# mcb-enhancer-v3.net
KiCad netlist of a schematic drawn in EAGLE
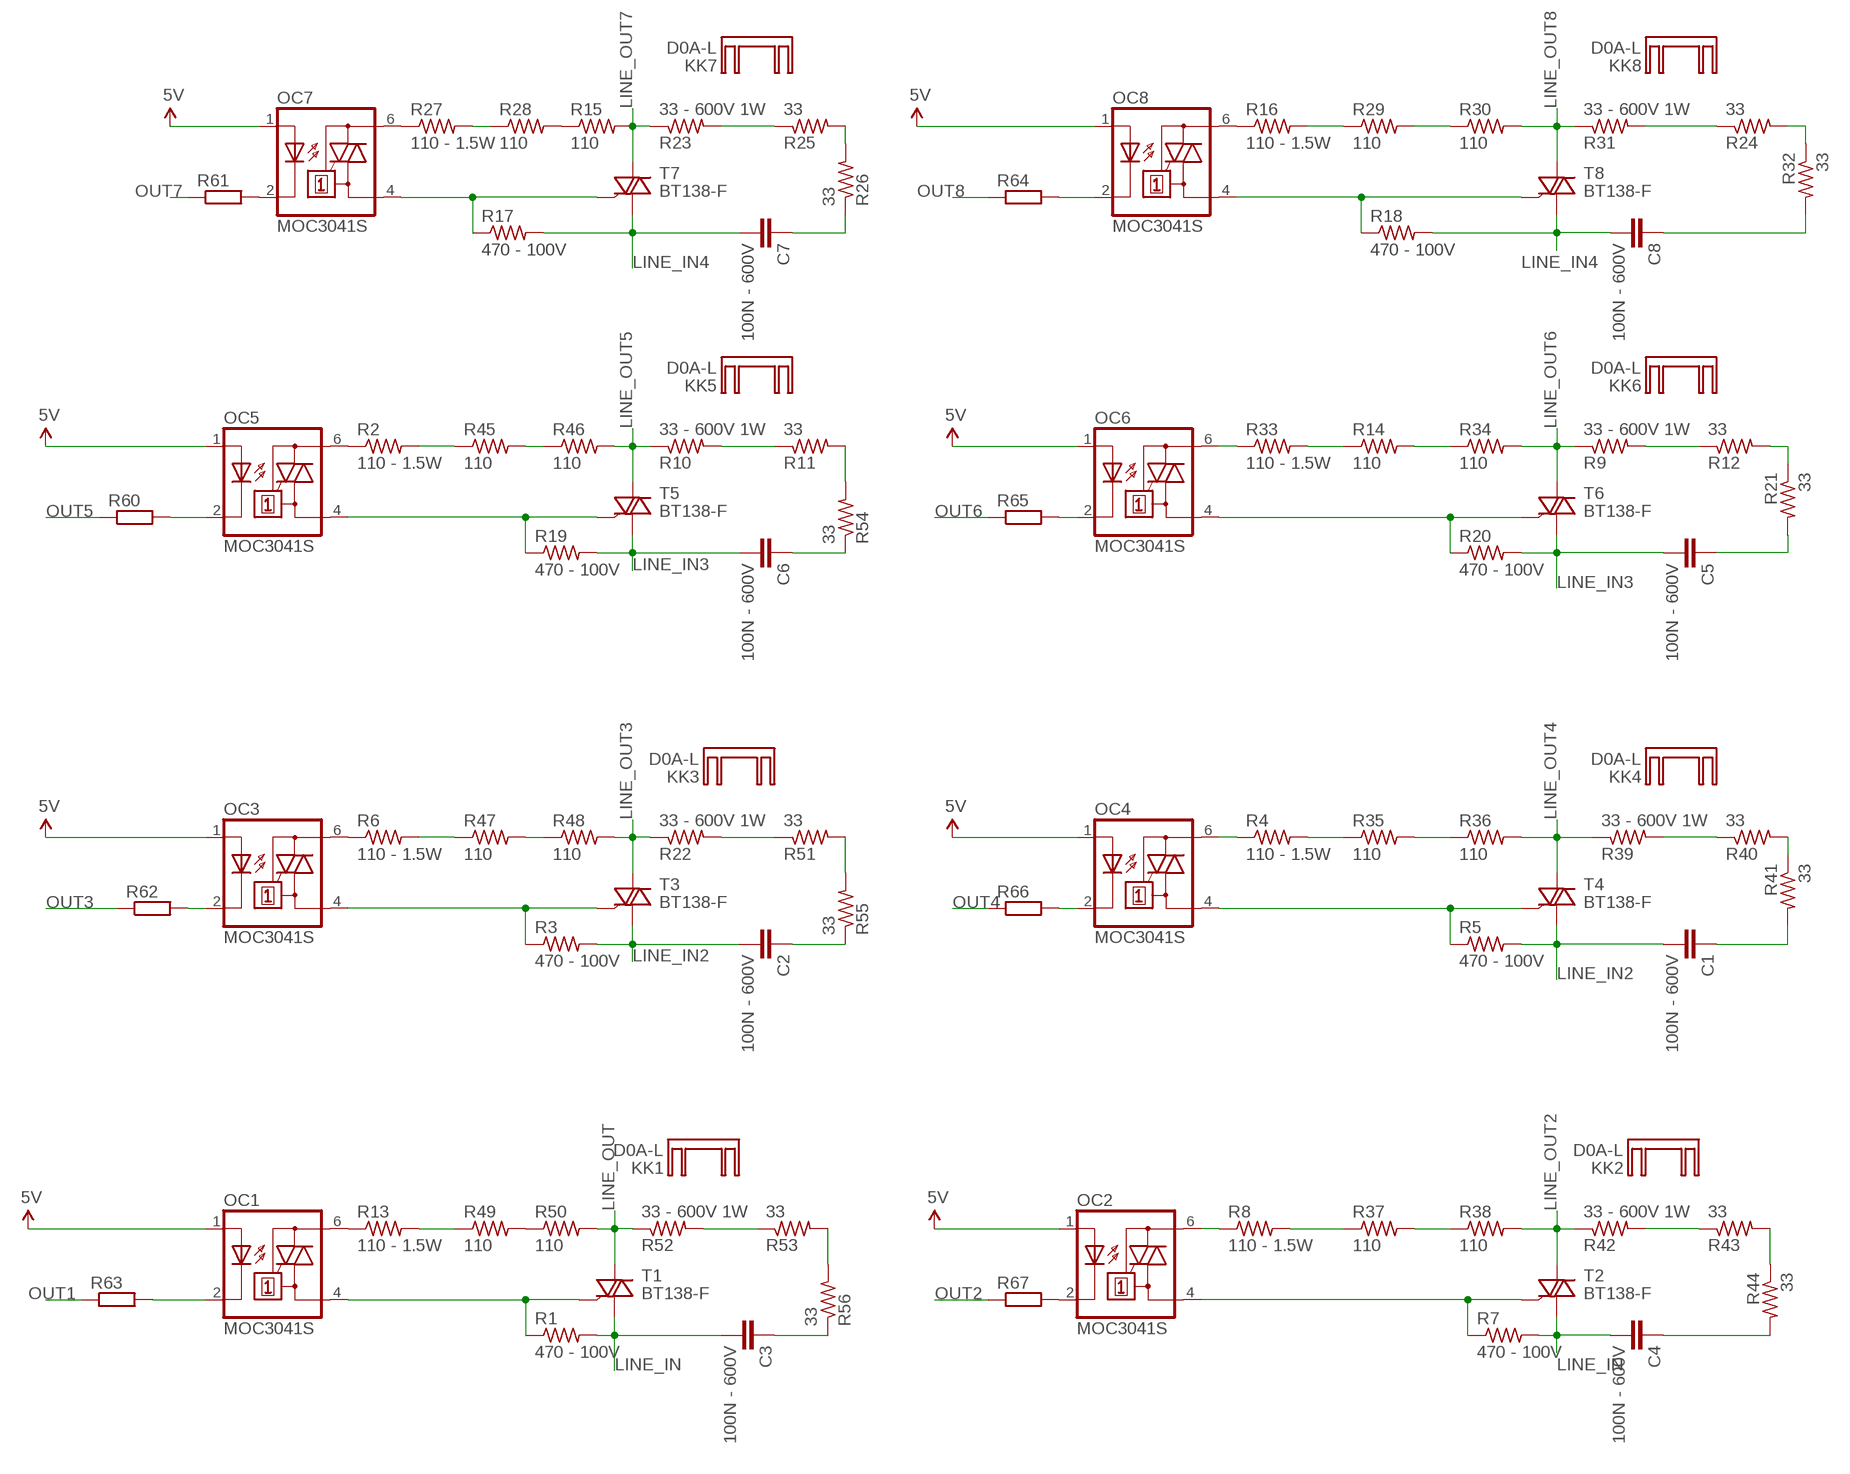
[diagram p0: schematic, sheet 1]

(export (version "E")
  (design (tool "Eeschema 10.0.6"))
  (components
    (comp (ref "C1")
      (value "100N - 600V")
      (footprint "eagle-import:C050-030X075")
      (libsource (lib "eagle-import") (part "C-EU050-030X075"))
    )
    (comp (ref "C2")
      (value "100N - 600V")
      (footprint "eagle-import:C050-030X075")
      (libsource (lib "eagle-import") (part "C-EU050-030X075"))
    )
    (comp (ref "C3")
      (value "100N - 600V")
      (footprint "eagle-import:C050-030X075")
      (libsource (lib "eagle-import") (part "C-EU050-030X075"))
    )
    (comp (ref "C4")
      (value "100N - 600V")
      (footprint "eagle-import:C050-030X075")
      (libsource (lib "eagle-import") (part "C-EU050-030X075"))
    )
    (comp (ref "C5")
      (value "100N - 600V")
      (footprint "eagle-import:C050-030X075")
      (libsource (lib "eagle-import") (part "C-EU050-030X075"))
    )
    (comp (ref "C6")
      (value "100N - 600V")
      (footprint "eagle-import:C050-030X075")
      (libsource (lib "eagle-import") (part "C-EU050-030X075"))
    )
    (comp (ref "C7")
      (value "100N - 600V")
      (footprint "eagle-import:C050-030X075")
      (libsource (lib "eagle-import") (part "C-EU050-030X075"))
    )
    (comp (ref "C8")
      (value "100N - 600V")
      (footprint "eagle-import:C050-030X075")
      (libsource (lib "eagle-import") (part "C-EU050-030X075"))
    )
    (comp (ref "KK1")
      (value "D0A-L")
      (footprint "eagle-import:D02A-L")
      (libsource (lib "eagle-import") (part "D0A-L"))
    )
    (comp (ref "KK2")
      (value "D0A-L")
      (footprint "eagle-import:D02A-L")
      (libsource (lib "eagle-import") (part "D0A-L"))
    )
    (comp (ref "KK3")
      (value "D0A-L")
      (footprint "eagle-import:D02A-L")
      (libsource (lib "eagle-import") (part "D0A-L"))
    )
    (comp (ref "KK4")
      (value "D0A-L")
      (footprint "eagle-import:D02A-L")
      (libsource (lib "eagle-import") (part "D0A-L"))
    )
    (comp (ref "KK5")
      (value "D0A-L")
      (footprint "eagle-import:D02A-L")
      (libsource (lib "eagle-import") (part "D0A-L"))
    )
    (comp (ref "KK6")
      (value "D0A-L")
      (footprint "eagle-import:D02A-L")
      (libsource (lib "eagle-import") (part "D0A-L"))
    )
    (comp (ref "KK7")
      (value "D0A-L")
      (footprint "eagle-import:D02A-L")
      (libsource (lib "eagle-import") (part "D0A-L"))
    )
    (comp (ref "KK8")
      (value "D0A-L")
      (footprint "eagle-import:D02A-L")
      (libsource (lib "eagle-import") (part "D0A-L"))
    )
    (comp (ref "OC1")
      (value "MOC3041S")
      (footprint "eagle-import:DIL6-SMD")
      (fields
        (field (name "MF") "FAIRCHILD SEMICONDUCTOR")
        (field (name "MPN") "MOC3041S-M")
        (field (name "MPN_1") "MOC3033S-M")
        (field (name "OC_FARNELL") "unknown")
        (field (name "OC_NEWARK") "05C2878")
      )
      (libsource (lib "eagle-import") (part "MOC30S41"))
    )
    (comp (ref "OC2")
      (value "MOC3041S")
      (footprint "eagle-import:DIL6-SMD")
      (fields
        (field (name "MF") "FAIRCHILD SEMICONDUCTOR")
        (field (name "MPN") "MOC3041S-M")
        (field (name "MPN_1") "MOC3033S-M")
        (field (name "OC_FARNELL") "unknown")
        (field (name "OC_NEWARK") "05C2878")
      )
      (libsource (lib "eagle-import") (part "MOC30S41"))
    )
    (comp (ref "OC3")
      (value "MOC3041S")
      (footprint "eagle-import:DIL6-SMD")
      (fields
        (field (name "MF") "FAIRCHILD SEMICONDUCTOR")
        (field (name "MPN") "MOC3041S-M")
        (field (name "MPN_1") "MOC3033S-M")
        (field (name "OC_FARNELL") "unknown")
        (field (name "OC_NEWARK") "05C2878")
      )
      (libsource (lib "eagle-import") (part "MOC30S41"))
    )
    (comp (ref "OC4")
      (value "MOC3041S")
      (footprint "eagle-import:DIL6-SMD")
      (fields
        (field (name "MF") "FAIRCHILD SEMICONDUCTOR")
        (field (name "MPN") "MOC3041S-M")
        (field (name "MPN_1") "MOC3033S-M")
        (field (name "OC_FARNELL") "unknown")
        (field (name "OC_NEWARK") "05C2878")
      )
      (libsource (lib "eagle-import") (part "MOC30S41"))
    )
    (comp (ref "OC5")
      (value "MOC3041S")
      (footprint "eagle-import:DIL6-SMD")
      (fields
        (field (name "MF") "FAIRCHILD SEMICONDUCTOR")
        (field (name "MPN") "MOC3041S-M")
        (field (name "MPN_1") "MOC3033S-M")
        (field (name "OC_FARNELL") "unknown")
        (field (name "OC_NEWARK") "05C2878")
      )
      (libsource (lib "eagle-import") (part "MOC30S41"))
    )
    (comp (ref "OC6")
      (value "MOC3041S")
      (footprint "eagle-import:DIL6-SMD")
      (fields
        (field (name "MF") "FAIRCHILD SEMICONDUCTOR")
        (field (name "MPN") "MOC3041S-M")
        (field (name "MPN_1") "MOC3033S-M")
        (field (name "OC_FARNELL") "unknown")
        (field (name "OC_NEWARK") "05C2878")
      )
      (libsource (lib "eagle-import") (part "MOC30S41"))
    )
    (comp (ref "OC7")
      (value "MOC3041S")
      (footprint "eagle-import:DIL6-SMD")
      (fields
        (field (name "MF") "FAIRCHILD SEMICONDUCTOR")
        (field (name "MPN") "MOC3041S-M")
        (field (name "MPN_1") "MOC3033S-M")
        (field (name "OC_FARNELL") "unknown")
        (field (name "OC_NEWARK") "05C2878")
      )
      (libsource (lib "eagle-import") (part "MOC30S41"))
    )
    (comp (ref "OC8")
      (value "MOC3041S")
      (footprint "eagle-import:DIL6-SMD")
      (fields
        (field (name "MF") "FAIRCHILD SEMICONDUCTOR")
        (field (name "MPN") "MOC3041S-M")
        (field (name "MPN_1") "MOC3033S-M")
        (field (name "OC_FARNELL") "unknown")
        (field (name "OC_NEWARK") "05C2878")
      )
      (libsource (lib "eagle-import") (part "MOC30S41"))
    )
    (comp (ref "R1")
      (value "470 - 100V")
      (footprint "eagle-import:R1206")
      (libsource (lib "eagle-import") (part "R-US_R1206"))
    )
    (comp (ref "R2")
      (value "110 - 1.5W")
      (footprint "eagle-import:R2512")
      (libsource (lib "eagle-import") (part "R-US_R2512"))
    )
    (comp (ref "R3")
      (value "470 - 100V")
      (footprint "eagle-import:R1206")
      (libsource (lib "eagle-import") (part "R-US_R1206"))
    )
    (comp (ref "R4")
      (value "110 - 1.5W")
      (footprint "eagle-import:R2512")
      (libsource (lib "eagle-import") (part "R-US_R2512"))
    )
    (comp (ref "R5")
      (value "470 - 100V")
      (footprint "eagle-import:R1206")
      (libsource (lib "eagle-import") (part "R-US_R1206"))
    )
    (comp (ref "R6")
      (value "110 - 1.5W")
      (footprint "eagle-import:R2512")
      (libsource (lib "eagle-import") (part "R-US_R2512"))
    )
    (comp (ref "R7")
      (value "470 - 100V")
      (footprint "eagle-import:R1206")
      (libsource (lib "eagle-import") (part "R-US_R1206"))
    )
    (comp (ref "R8")
      (value "110 - 1.5W")
      (footprint "eagle-import:R2512")
      (libsource (lib "eagle-import") (part "R-US_R2512"))
    )
    (comp (ref "R9")
      (value "33 - 600V 1W")
      (footprint "eagle-import:R1206")
      (libsource (lib "eagle-import") (part "R-US_R1206"))
    )
    (comp (ref "R10")
      (value "33 - 600V 1W")
      (footprint "eagle-import:R1206")
      (libsource (lib "eagle-import") (part "R-US_R1206"))
    )
    (comp (ref "R11")
      (value "33")
      (footprint "eagle-import:R1206")
      (libsource (lib "eagle-import") (part "R-US_R1206"))
    )
    (comp (ref "R12")
      (value "33")
      (footprint "eagle-import:R1206")
      (libsource (lib "eagle-import") (part "R-US_R1206"))
    )
    (comp (ref "R13")
      (value "110 - 1.5W")
      (footprint "eagle-import:R2512")
      (libsource (lib "eagle-import") (part "R-US_R2512"))
    )
    (comp (ref "R14")
      (value "110")
      (footprint "eagle-import:R2512")
      (libsource (lib "eagle-import") (part "R-US_R2512"))
    )
    (comp (ref "R15")
      (value "110")
      (footprint "eagle-import:R2512")
      (libsource (lib "eagle-import") (part "R-US_R2512"))
    )
    (comp (ref "R16")
      (value "110 - 1.5W")
      (footprint "eagle-import:R2512")
      (libsource (lib "eagle-import") (part "R-US_R2512"))
    )
    (comp (ref "R17")
      (value "470 - 100V")
      (footprint "eagle-import:R1206")
      (libsource (lib "eagle-import") (part "R-US_R1206"))
    )
    (comp (ref "R18")
      (value "470 - 100V")
      (footprint "eagle-import:R1206")
      (libsource (lib "eagle-import") (part "R-US_R1206"))
    )
    (comp (ref "R19")
      (value "470 - 100V")
      (footprint "eagle-import:R1206")
      (libsource (lib "eagle-import") (part "R-US_R1206"))
    )
    (comp (ref "R20")
      (value "470 - 100V")
      (footprint "eagle-import:R1206")
      (libsource (lib "eagle-import") (part "R-US_R1206"))
    )
    (comp (ref "R21")
      (value "33")
      (footprint "eagle-import:R1206")
      (libsource (lib "eagle-import") (part "R-US_R1206"))
    )
    (comp (ref "R22")
      (value "33 - 600V 1W")
      (footprint "eagle-import:R1206")
      (libsource (lib "eagle-import") (part "R-US_R1206"))
    )
    (comp (ref "R23")
      (value "33 - 600V 1W")
      (footprint "eagle-import:R1206")
      (libsource (lib "eagle-import") (part "R-US_R1206"))
    )
    (comp (ref "R24")
      (value "33")
      (footprint "eagle-import:R1206")
      (libsource (lib "eagle-import") (part "R-US_R1206"))
    )
    (comp (ref "R25")
      (value "33")
      (footprint "eagle-import:R1206")
      (libsource (lib "eagle-import") (part "R-US_R1206"))
    )
    (comp (ref "R26")
      (value "33")
      (footprint "eagle-import:R1206")
      (libsource (lib "eagle-import") (part "R-US_R1206"))
    )
    (comp (ref "R27")
      (value "110 - 1.5W")
      (footprint "eagle-import:R2512")
      (libsource (lib "eagle-import") (part "R-US_R2512"))
    )
    (comp (ref "R28")
      (value "110")
      (footprint "eagle-import:R2512")
      (libsource (lib "eagle-import") (part "R-US_R2512"))
    )
    (comp (ref "R29")
      (value "110")
      (footprint "eagle-import:R2512")
      (libsource (lib "eagle-import") (part "R-US_R2512"))
    )
    (comp (ref "R30")
      (value "110")
      (footprint "eagle-import:R2512")
      (libsource (lib "eagle-import") (part "R-US_R2512"))
    )
    (comp (ref "R31")
      (value "33 - 600V 1W")
      (footprint "eagle-import:R1206")
      (libsource (lib "eagle-import") (part "R-US_R1206"))
    )
    (comp (ref "R32")
      (value "33")
      (footprint "eagle-import:R1206")
      (libsource (lib "eagle-import") (part "R-US_R1206"))
    )
    (comp (ref "R33")
      (value "110 - 1.5W")
      (footprint "eagle-import:R2512")
      (libsource (lib "eagle-import") (part "R-US_R2512"))
    )
    (comp (ref "R34")
      (value "110")
      (footprint "eagle-import:R2512")
      (libsource (lib "eagle-import") (part "R-US_R2512"))
    )
    (comp (ref "R35")
      (value "110")
      (footprint "eagle-import:R2512")
      (libsource (lib "eagle-import") (part "R-US_R2512"))
    )
    (comp (ref "R36")
      (value "110")
      (footprint "eagle-import:R2512")
      (libsource (lib "eagle-import") (part "R-US_R2512"))
    )
    (comp (ref "R37")
      (value "110")
      (footprint "eagle-import:R2512")
      (libsource (lib "eagle-import") (part "R-US_R2512"))
    )
    (comp (ref "R38")
      (value "110")
      (footprint "eagle-import:R2512")
      (libsource (lib "eagle-import") (part "R-US_R2512"))
    )
    (comp (ref "R39")
      (value "33 - 600V 1W")
      (footprint "eagle-import:R1206")
      (libsource (lib "eagle-import") (part "R-US_R1206"))
    )
    (comp (ref "R40")
      (value "33")
      (footprint "eagle-import:R1206")
      (libsource (lib "eagle-import") (part "R-US_R1206"))
    )
    (comp (ref "R41")
      (value "33")
      (footprint "eagle-import:R1206")
      (libsource (lib "eagle-import") (part "R-US_R1206"))
    )
    (comp (ref "R42")
      (value "33 - 600V 1W")
      (footprint "eagle-import:R1206")
      (libsource (lib "eagle-import") (part "R-US_R1206"))
    )
    (comp (ref "R43")
      (value "33")
      (footprint "eagle-import:R1206")
      (libsource (lib "eagle-import") (part "R-US_R1206"))
    )
    (comp (ref "R44")
      (value "33")
      (footprint "eagle-import:R1206")
      (libsource (lib "eagle-import") (part "R-US_R1206"))
    )
    (comp (ref "R45")
      (value "110")
      (footprint "eagle-import:R2512")
      (libsource (lib "eagle-import") (part "R-US_R2512"))
    )
    (comp (ref "R46")
      (value "110")
      (footprint "eagle-import:R2512")
      (libsource (lib "eagle-import") (part "R-US_R2512"))
    )
    (comp (ref "R47")
      (value "110")
      (footprint "eagle-import:R2512")
      (libsource (lib "eagle-import") (part "R-US_R2512"))
    )
    (comp (ref "R48")
      (value "110")
      (footprint "eagle-import:R2512")
      (libsource (lib "eagle-import") (part "R-US_R2512"))
    )
    (comp (ref "R49")
      (value "110")
      (footprint "eagle-import:R2512")
      (libsource (lib "eagle-import") (part "R-US_R2512"))
    )
    (comp (ref "R50")
      (value "110")
      (footprint "eagle-import:R2512")
      (libsource (lib "eagle-import") (part "R-US_R2512"))
    )
    (comp (ref "R51")
      (value "33")
      (footprint "eagle-import:R1206")
      (libsource (lib "eagle-import") (part "R-US_R1206"))
    )
    (comp (ref "R52")
      (value "33 - 600V 1W")
      (footprint "eagle-import:R1206")
      (libsource (lib "eagle-import") (part "R-US_R1206"))
    )
    (comp (ref "R53")
      (value "33")
      (footprint "eagle-import:R1206")
      (libsource (lib "eagle-import") (part "R-US_R1206"))
    )
    (comp (ref "R54")
      (value "33")
      (footprint "eagle-import:R1206")
      (libsource (lib "eagle-import") (part "R-US_R1206"))
    )
    (comp (ref "R55")
      (value "33")
      (footprint "eagle-import:R1206")
      (libsource (lib "eagle-import") (part "R-US_R1206"))
    )
    (comp (ref "R56")
      (value "33")
      (footprint "eagle-import:R1206")
      (libsource (lib "eagle-import") (part "R-US_R1206"))
    )
    (comp (ref "R60")
      (value "R-EU_R0603")
      (footprint "eagle-import:R0603")
      (libsource (lib "eagle-import") (part "R-EU_R0603"))
    )
    (comp (ref "R61")
      (value "R-EU_R0603")
      (footprint "eagle-import:R0603")
      (libsource (lib "eagle-import") (part "R-EU_R0603"))
    )
    (comp (ref "R62")
      (value "R-EU_R0603")
      (footprint "eagle-import:R0603")
      (libsource (lib "eagle-import") (part "R-EU_R0603"))
    )
    (comp (ref "R63")
      (value "R-EU_R0603")
      (footprint "eagle-import:R0603")
      (libsource (lib "eagle-import") (part "R-EU_R0603"))
    )
    (comp (ref "R64")
      (value "R-EU_R0603")
      (footprint "eagle-import:R0603")
      (libsource (lib "eagle-import") (part "R-EU_R0603"))
    )
    (comp (ref "R65")
      (value "R-EU_R0603")
      (footprint "eagle-import:R0603")
      (libsource (lib "eagle-import") (part "R-EU_R0603"))
    )
    (comp (ref "R66")
      (value "R-EU_R0603")
      (footprint "eagle-import:R0603")
      (libsource (lib "eagle-import") (part "R-EU_R0603"))
    )
    (comp (ref "R67")
      (value "R-EU_R0603")
      (footprint "eagle-import:R0603")
      (libsource (lib "eagle-import") (part "R-EU_R0603"))
    )
    (comp (ref "T1")
      (value "BT138-F")
      (footprint "eagle-import:TO220BF")
      (libsource (lib "eagle-import") (part "BT138-F"))
    )
    (comp (ref "T2")
      (value "BT138-F")
      (footprint "eagle-import:TO220BF")
      (libsource (lib "eagle-import") (part "BT138-F"))
    )
    (comp (ref "T3")
      (value "BT138-F")
      (footprint "eagle-import:TO220BF")
      (libsource (lib "eagle-import") (part "BT138-F"))
    )
    (comp (ref "T4")
      (value "BT138-F")
      (footprint "eagle-import:TO220BF")
      (libsource (lib "eagle-import") (part "BT138-F"))
    )
    (comp (ref "T5")
      (value "BT138-F")
      (footprint "eagle-import:TO220BF")
      (libsource (lib "eagle-import") (part "BT138-F"))
    )
    (comp (ref "T6")
      (value "BT138-F")
      (footprint "eagle-import:TO220BF")
      (libsource (lib "eagle-import") (part "BT138-F"))
    )
    (comp (ref "T7")
      (value "BT138-F")
      (footprint "eagle-import:TO220BF")
      (libsource (lib "eagle-import") (part "BT138-F"))
    )
    (comp (ref "T8")
      (value "BT138-F")
      (footprint "eagle-import:TO220BF")
      (libsource (lib "eagle-import") (part "BT138-F"))
    )
  )
  (nets
    (net (code "1") (name "/LINE_IN") (class "Default")
      (node (ref "C3") (pin "2") (pinfunction "2_2") (pintype "passive"))
      (node (ref "C4") (pin "2") (pinfunction "2_2") (pintype "passive"))
      (node (ref "R1") (pin "2") (pinfunction "2_2") (pintype "passive"))
      (node (ref "R7") (pin "2") (pinfunction "2_2") (pintype "passive"))
      (node (ref "T1") (pin "T1") (pinfunction "A1_T1") (pintype "passive"))
      (node (ref "T2") (pin "T1") (pinfunction "A1_T1") (pintype "passive"))
    )
    (net (code "2") (name "/LINE_IN2") (class "Default")
      (node (ref "C1") (pin "2") (pinfunction "2_2") (pintype "passive"))
      (node (ref "C2") (pin "2") (pinfunction "2_2") (pintype "passive"))
      (node (ref "R3") (pin "2") (pinfunction "2_2") (pintype "passive"))
      (node (ref "R5") (pin "2") (pinfunction "2_2") (pintype "passive"))
      (node (ref "T3") (pin "T1") (pinfunction "A1_T1") (pintype "passive"))
      (node (ref "T4") (pin "T1") (pinfunction "A1_T1") (pintype "passive"))
    )
    (net (code "3") (name "/LINE_IN3") (class "Default")
      (node (ref "C5") (pin "2") (pinfunction "2_2") (pintype "passive"))
      (node (ref "C6") (pin "2") (pinfunction "2_2") (pintype "passive"))
      (node (ref "R19") (pin "2") (pinfunction "2_2") (pintype "passive"))
      (node (ref "R20") (pin "2") (pinfunction "2_2") (pintype "passive"))
      (node (ref "T5") (pin "T1") (pinfunction "A1_T1") (pintype "passive"))
      (node (ref "T6") (pin "T1") (pinfunction "A1_T1") (pintype "passive"))
    )
    (net (code "4") (name "/LINE_IN4") (class "Default")
      (node (ref "C7") (pin "2") (pinfunction "2_2") (pintype "passive"))
      (node (ref "C8") (pin "2") (pinfunction "2_2") (pintype "passive"))
      (node (ref "R17") (pin "2") (pinfunction "2_2") (pintype "passive"))
      (node (ref "R18") (pin "2") (pinfunction "2_2") (pintype "passive"))
      (node (ref "T7") (pin "T1") (pinfunction "A1_T1") (pintype "passive"))
      (node (ref "T8") (pin "T1") (pinfunction "A1_T1") (pintype "passive"))
    )
    (net (code "5") (name "/LINE_OUT") (class "Default")
      (node (ref "R50") (pin "2") (pinfunction "2_2") (pintype "passive"))
      (node (ref "R52") (pin "1") (pinfunction "1_1") (pintype "passive"))
      (node (ref "T1") (pin "T2") (pinfunction "A2_T2") (pintype "passive"))
    )
    (net (code "6") (name "/LINE_OUT2") (class "Default")
      (node (ref "R38") (pin "2") (pinfunction "2_2") (pintype "passive"))
      (node (ref "R42") (pin "1") (pinfunction "1_1") (pintype "passive"))
      (node (ref "T2") (pin "T2") (pinfunction "A2_T2") (pintype "passive"))
    )
    (net (code "7") (name "/LINE_OUT3") (class "Default")
      (node (ref "R22") (pin "1") (pinfunction "1_1") (pintype "passive"))
      (node (ref "R48") (pin "2") (pinfunction "2_2") (pintype "passive"))
      (node (ref "T3") (pin "T2") (pinfunction "A2_T2") (pintype "passive"))
    )
    (net (code "8") (name "/LINE_OUT4") (class "Default")
      (node (ref "R36") (pin "2") (pinfunction "2_2") (pintype "passive"))
      (node (ref "R39") (pin "1") (pinfunction "1_1") (pintype "passive"))
      (node (ref "T4") (pin "T2") (pinfunction "A2_T2") (pintype "passive"))
    )
    (net (code "9") (name "/LINE_OUT5") (class "Default")
      (node (ref "R10") (pin "1") (pinfunction "1_1") (pintype "passive"))
      (node (ref "R46") (pin "2") (pinfunction "2_2") (pintype "passive"))
      (node (ref "T5") (pin "T2") (pinfunction "A2_T2") (pintype "passive"))
    )
    (net (code "10") (name "/LINE_OUT6") (class "Default")
      (node (ref "R34") (pin "2") (pinfunction "2_2") (pintype "passive"))
      (node (ref "R9") (pin "1") (pinfunction "1_1") (pintype "passive"))
      (node (ref "T6") (pin "T2") (pinfunction "A2_T2") (pintype "passive"))
    )
    (net (code "11") (name "/LINE_OUT7") (class "Default")
      (node (ref "R15") (pin "2") (pinfunction "2_2") (pintype "passive"))
      (node (ref "R23") (pin "1") (pinfunction "1_1") (pintype "passive"))
      (node (ref "T7") (pin "T2") (pinfunction "A2_T2") (pintype "passive"))
    )
    (net (code "12") (name "/LINE_OUT8") (class "Default")
      (node (ref "R30") (pin "2") (pinfunction "2_2") (pintype "passive"))
      (node (ref "R31") (pin "1") (pinfunction "1_1") (pintype "passive"))
      (node (ref "T8") (pin "T2") (pinfunction "A2_T2") (pintype "passive"))
    )
    (net (code "13") (name "/OUT1") (class "Default")
      (node (ref "R63") (pin "1") (pinfunction "1_1") (pintype "passive"))
    )
    (net (code "14") (name "/OUT2") (class "Default")
      (node (ref "R67") (pin "1") (pinfunction "1_1") (pintype "passive"))
    )
    (net (code "15") (name "/OUT3") (class "Default")
      (node (ref "R62") (pin "1") (pinfunction "1_1") (pintype "passive"))
    )
    (net (code "16") (name "/OUT4") (class "Default")
      (node (ref "R66") (pin "1") (pinfunction "1_1") (pintype "passive"))
    )
    (net (code "17") (name "/OUT5") (class "Default")
      (node (ref "R60") (pin "1") (pinfunction "1_1") (pintype "passive"))
    )
    (net (code "18") (name "/OUT6") (class "Default")
      (node (ref "R65") (pin "1") (pinfunction "1_1") (pintype "passive"))
    )
    (net (code "19") (name "/OUT7") (class "Default")
      (node (ref "R61") (pin "1") (pinfunction "1_1") (pintype "passive"))
    )
    (net (code "20") (name "/OUT8") (class "Default")
      (node (ref "R64") (pin "1") (pinfunction "1_1") (pintype "passive"))
    )
    (net (code "21") (name "5V") (class "Default")
      (node (ref "OC1") (pin "1") (pinfunction "A_1") (pintype "passive"))
      (node (ref "OC2") (pin "1") (pinfunction "A_1") (pintype "passive"))
      (node (ref "OC3") (pin "1") (pinfunction "A_1") (pintype "passive"))
      (node (ref "OC4") (pin "1") (pinfunction "A_1") (pintype "passive"))
      (node (ref "OC5") (pin "1") (pinfunction "A_1") (pintype "passive"))
      (node (ref "OC6") (pin "1") (pinfunction "A_1") (pintype "passive"))
      (node (ref "OC7") (pin "1") (pinfunction "A_1") (pintype "passive"))
      (node (ref "OC8") (pin "1") (pinfunction "A_1") (pintype "passive"))
    )
    (net (code "22") (name "Net-(C1-Pad1)") (class "Default")
      (node (ref "C1") (pin "1") (pinfunction "1_1") (pintype "passive"))
      (node (ref "R41") (pin "2") (pinfunction "2_2") (pintype "passive"))
    )
    (net (code "23") (name "Net-(C2-Pad1)") (class "Default")
      (node (ref "C2") (pin "1") (pinfunction "1_1") (pintype "passive"))
      (node (ref "R55") (pin "1") (pinfunction "1_1") (pintype "passive"))
    )
    (net (code "24") (name "Net-(C3-Pad1)") (class "Default")
      (node (ref "C3") (pin "1") (pinfunction "1_1") (pintype "passive"))
      (node (ref "R56") (pin "1") (pinfunction "1_1") (pintype "passive"))
    )
    (net (code "25") (name "Net-(C4-Pad1)") (class "Default")
      (node (ref "C4") (pin "1") (pinfunction "1_1") (pintype "passive"))
      (node (ref "R44") (pin "2") (pinfunction "2_2") (pintype "passive"))
    )
    (net (code "26") (name "Net-(C5-Pad1)") (class "Default")
      (node (ref "C5") (pin "1") (pinfunction "1_1") (pintype "passive"))
      (node (ref "R21") (pin "2") (pinfunction "2_2") (pintype "passive"))
    )
    (net (code "27") (name "Net-(C6-Pad1)") (class "Default")
      (node (ref "C6") (pin "1") (pinfunction "1_1") (pintype "passive"))
      (node (ref "R54") (pin "1") (pinfunction "1_1") (pintype "passive"))
    )
    (net (code "28") (name "Net-(C7-Pad1)") (class "Default")
      (node (ref "C7") (pin "1") (pinfunction "1_1") (pintype "passive"))
      (node (ref "R26") (pin "1") (pinfunction "1_1") (pintype "passive"))
    )
    (net (code "29") (name "Net-(C8-Pad1)") (class "Default")
      (node (ref "C8") (pin "1") (pinfunction "1_1") (pintype "passive"))
      (node (ref "R32") (pin "2") (pinfunction "2_2") (pintype "passive"))
    )
    (net (code "30") (name "Net-(OC1-A1)") (class "Default")
      (node (ref "OC1") (pin "4") (pinfunction "A1_4") (pintype "passive"))
      (node (ref "R1") (pin "1") (pinfunction "1_1") (pintype "passive"))
      (node (ref "T1") (pin "G") (pinfunction "G_G") (pintype "passive"))
    )
    (net (code "31") (name "Net-(OC1-A2)") (class "Default")
      (node (ref "OC1") (pin "6") (pinfunction "A2_6") (pintype "passive"))
      (node (ref "R13") (pin "1") (pinfunction "1_1") (pintype "passive"))
    )
    (net (code "32") (name "Net-(OC1-C)") (class "Default")
      (node (ref "OC1") (pin "2") (pinfunction "C_2") (pintype "passive"))
      (node (ref "R63") (pin "2") (pinfunction "2_2") (pintype "passive"))
    )
    (net (code "33") (name "Net-(OC2-A1)") (class "Default")
      (node (ref "OC2") (pin "4") (pinfunction "A1_4") (pintype "passive"))
      (node (ref "R7") (pin "1") (pinfunction "1_1") (pintype "passive"))
      (node (ref "T2") (pin "G") (pinfunction "G_G") (pintype "passive"))
    )
    (net (code "34") (name "Net-(OC2-A2)") (class "Default")
      (node (ref "OC2") (pin "6") (pinfunction "A2_6") (pintype "passive"))
      (node (ref "R8") (pin "1") (pinfunction "1_1") (pintype "passive"))
    )
    (net (code "35") (name "Net-(OC2-C)") (class "Default")
      (node (ref "OC2") (pin "2") (pinfunction "C_2") (pintype "passive"))
      (node (ref "R67") (pin "2") (pinfunction "2_2") (pintype "passive"))
    )
    (net (code "36") (name "Net-(OC3-A1)") (class "Default")
      (node (ref "OC3") (pin "4") (pinfunction "A1_4") (pintype "passive"))
      (node (ref "R3") (pin "1") (pinfunction "1_1") (pintype "passive"))
      (node (ref "T3") (pin "G") (pinfunction "G_G") (pintype "passive"))
    )
    (net (code "37") (name "Net-(OC3-A2)") (class "Default")
      (node (ref "OC3") (pin "6") (pinfunction "A2_6") (pintype "passive"))
      (node (ref "R6") (pin "1") (pinfunction "1_1") (pintype "passive"))
    )
    (net (code "38") (name "Net-(OC3-C)") (class "Default")
      (node (ref "OC3") (pin "2") (pinfunction "C_2") (pintype "passive"))
      (node (ref "R62") (pin "2") (pinfunction "2_2") (pintype "passive"))
    )
    (net (code "39") (name "Net-(OC4-A1)") (class "Default")
      (node (ref "OC4") (pin "4") (pinfunction "A1_4") (pintype "passive"))
      (node (ref "R5") (pin "1") (pinfunction "1_1") (pintype "passive"))
      (node (ref "T4") (pin "G") (pinfunction "G_G") (pintype "passive"))
    )
    (net (code "40") (name "Net-(OC4-A2)") (class "Default")
      (node (ref "OC4") (pin "6") (pinfunction "A2_6") (pintype "passive"))
      (node (ref "R4") (pin "1") (pinfunction "1_1") (pintype "passive"))
    )
    (net (code "41") (name "Net-(OC4-C)") (class "Default")
      (node (ref "OC4") (pin "2") (pinfunction "C_2") (pintype "passive"))
      (node (ref "R66") (pin "2") (pinfunction "2_2") (pintype "passive"))
    )
    (net (code "42") (name "Net-(OC5-A1)") (class "Default")
      (node (ref "OC5") (pin "4") (pinfunction "A1_4") (pintype "passive"))
      (node (ref "R19") (pin "1") (pinfunction "1_1") (pintype "passive"))
      (node (ref "T5") (pin "G") (pinfunction "G_G") (pintype "passive"))
    )
    (net (code "43") (name "Net-(OC5-A2)") (class "Default")
      (node (ref "OC5") (pin "6") (pinfunction "A2_6") (pintype "passive"))
      (node (ref "R2") (pin "1") (pinfunction "1_1") (pintype "passive"))
    )
    (net (code "44") (name "Net-(OC5-C)") (class "Default")
      (node (ref "OC5") (pin "2") (pinfunction "C_2") (pintype "passive"))
      (node (ref "R60") (pin "2") (pinfunction "2_2") (pintype "passive"))
    )
    (net (code "45") (name "Net-(OC6-A1)") (class "Default")
      (node (ref "OC6") (pin "4") (pinfunction "A1_4") (pintype "passive"))
      (node (ref "R20") (pin "1") (pinfunction "1_1") (pintype "passive"))
      (node (ref "T6") (pin "G") (pinfunction "G_G") (pintype "passive"))
    )
    (net (code "46") (name "Net-(OC6-A2)") (class "Default")
      (node (ref "OC6") (pin "6") (pinfunction "A2_6") (pintype "passive"))
      (node (ref "R33") (pin "1") (pinfunction "1_1") (pintype "passive"))
    )
    (net (code "47") (name "Net-(OC6-C)") (class "Default")
      (node (ref "OC6") (pin "2") (pinfunction "C_2") (pintype "passive"))
      (node (ref "R65") (pin "2") (pinfunction "2_2") (pintype "passive"))
    )
    (net (code "48") (name "Net-(OC7-A1)") (class "Default")
      (node (ref "OC7") (pin "4") (pinfunction "A1_4") (pintype "passive"))
      (node (ref "R17") (pin "1") (pinfunction "1_1") (pintype "passive"))
      (node (ref "T7") (pin "G") (pinfunction "G_G") (pintype "passive"))
    )
    (net (code "49") (name "Net-(OC7-A2)") (class "Default")
      (node (ref "OC7") (pin "6") (pinfunction "A2_6") (pintype "passive"))
      (node (ref "R27") (pin "1") (pinfunction "1_1") (pintype "passive"))
    )
    (net (code "50") (name "Net-(OC7-C)") (class "Default")
      (node (ref "OC7") (pin "2") (pinfunction "C_2") (pintype "passive"))
      (node (ref "R61") (pin "2") (pinfunction "2_2") (pintype "passive"))
    )
    (net (code "51") (name "Net-(OC8-A1)") (class "Default")
      (node (ref "OC8") (pin "4") (pinfunction "A1_4") (pintype "passive"))
      (node (ref "R18") (pin "1") (pinfunction "1_1") (pintype "passive"))
      (node (ref "T8") (pin "G") (pinfunction "G_G") (pintype "passive"))
    )
    (net (code "52") (name "Net-(OC8-A2)") (class "Default")
      (node (ref "OC8") (pin "6") (pinfunction "A2_6") (pintype "passive"))
      (node (ref "R16") (pin "1") (pinfunction "1_1") (pintype "passive"))
    )
    (net (code "53") (name "Net-(OC8-C)") (class "Default")
      (node (ref "OC8") (pin "2") (pinfunction "C_2") (pintype "passive"))
      (node (ref "R64") (pin "2") (pinfunction "2_2") (pintype "passive"))
    )
    (net (code "54") (name "Net-(R2-Pad2)") (class "Default")
      (node (ref "R2") (pin "2") (pinfunction "2_2") (pintype "passive"))
      (node (ref "R45") (pin "1") (pinfunction "1_1") (pintype "passive"))
    )
    (net (code "55") (name "Net-(R10-Pad2)") (class "Default")
      (node (ref "R10") (pin "2") (pinfunction "2_2") (pintype "passive"))
      (node (ref "R11") (pin "1") (pinfunction "1_1") (pintype "passive"))
    )
    (net (code "56") (name "Net-(R11-Pad2)") (class "Default")
      (node (ref "R11") (pin "2") (pinfunction "2_2") (pintype "passive"))
      (node (ref "R54") (pin "2") (pinfunction "2_2") (pintype "passive"))
    )
    (net (code "57") (name "Net-(R12-Pad1)") (class "Default")
      (node (ref "R12") (pin "1") (pinfunction "1_1") (pintype "passive"))
      (node (ref "R9") (pin "2") (pinfunction "2_2") (pintype "passive"))
    )
    (net (code "58") (name "Net-(R12-Pad2)") (class "Default")
      (node (ref "R12") (pin "2") (pinfunction "2_2") (pintype "passive"))
      (node (ref "R21") (pin "1") (pinfunction "1_1") (pintype "passive"))
    )
    (net (code "59") (name "Net-(R13-Pad2)") (class "Default")
      (node (ref "R13") (pin "2") (pinfunction "2_2") (pintype "passive"))
      (node (ref "R49") (pin "1") (pinfunction "1_1") (pintype "passive"))
    )
    (net (code "60") (name "Net-(R14-Pad1)") (class "Default")
      (node (ref "R14") (pin "1") (pinfunction "1_1") (pintype "passive"))
      (node (ref "R33") (pin "2") (pinfunction "2_2") (pintype "passive"))
    )
    (net (code "61") (name "Net-(R14-Pad2)") (class "Default")
      (node (ref "R14") (pin "2") (pinfunction "2_2") (pintype "passive"))
      (node (ref "R34") (pin "1") (pinfunction "1_1") (pintype "passive"))
    )
    (net (code "62") (name "Net-(R15-Pad1)") (class "Default")
      (node (ref "R15") (pin "1") (pinfunction "1_1") (pintype "passive"))
      (node (ref "R28") (pin "2") (pinfunction "2_2") (pintype "passive"))
    )
    (net (code "63") (name "Net-(R16-Pad2)") (class "Default")
      (node (ref "R16") (pin "2") (pinfunction "2_2") (pintype "passive"))
      (node (ref "R29") (pin "1") (pinfunction "1_1") (pintype "passive"))
    )
    (net (code "64") (name "Net-(R22-Pad2)") (class "Default")
      (node (ref "R22") (pin "2") (pinfunction "2_2") (pintype "passive"))
      (node (ref "R51") (pin "1") (pinfunction "1_1") (pintype "passive"))
    )
    (net (code "65") (name "Net-(R23-Pad2)") (class "Default")
      (node (ref "R23") (pin "2") (pinfunction "2_2") (pintype "passive"))
      (node (ref "R25") (pin "1") (pinfunction "1_1") (pintype "passive"))
    )
    (net (code "66") (name "Net-(R24-Pad1)") (class "Default")
      (node (ref "R24") (pin "1") (pinfunction "1_1") (pintype "passive"))
      (node (ref "R31") (pin "2") (pinfunction "2_2") (pintype "passive"))
    )
    (net (code "67") (name "Net-(R24-Pad2)") (class "Default")
      (node (ref "R24") (pin "2") (pinfunction "2_2") (pintype "passive"))
      (node (ref "R32") (pin "1") (pinfunction "1_1") (pintype "passive"))
    )
    (net (code "68") (name "Net-(R25-Pad2)") (class "Default")
      (node (ref "R25") (pin "2") (pinfunction "2_2") (pintype "passive"))
      (node (ref "R26") (pin "2") (pinfunction "2_2") (pintype "passive"))
    )
    (net (code "69") (name "Net-(R27-Pad2)") (class "Default")
      (node (ref "R27") (pin "2") (pinfunction "2_2") (pintype "passive"))
      (node (ref "R28") (pin "1") (pinfunction "1_1") (pintype "passive"))
    )
    (net (code "70") (name "Net-(R29-Pad2)") (class "Default")
      (node (ref "R29") (pin "2") (pinfunction "2_2") (pintype "passive"))
      (node (ref "R30") (pin "1") (pinfunction "1_1") (pintype "passive"))
    )
    (net (code "71") (name "Net-(R35-Pad1)") (class "Default")
      (node (ref "R35") (pin "1") (pinfunction "1_1") (pintype "passive"))
      (node (ref "R4") (pin "2") (pinfunction "2_2") (pintype "passive"))
    )
    (net (code "72") (name "Net-(R35-Pad2)") (class "Default")
      (node (ref "R35") (pin "2") (pinfunction "2_2") (pintype "passive"))
      (node (ref "R36") (pin "1") (pinfunction "1_1") (pintype "passive"))
    )
    (net (code "73") (name "Net-(R37-Pad1)") (class "Default")
      (node (ref "R37") (pin "1") (pinfunction "1_1") (pintype "passive"))
      (node (ref "R8") (pin "2") (pinfunction "2_2") (pintype "passive"))
    )
    (net (code "74") (name "Net-(R37-Pad2)") (class "Default")
      (node (ref "R37") (pin "2") (pinfunction "2_2") (pintype "passive"))
      (node (ref "R38") (pin "1") (pinfunction "1_1") (pintype "passive"))
    )
    (net (code "75") (name "Net-(R39-Pad2)") (class "Default")
      (node (ref "R39") (pin "2") (pinfunction "2_2") (pintype "passive"))
      (node (ref "R40") (pin "1") (pinfunction "1_1") (pintype "passive"))
    )
    (net (code "76") (name "Net-(R40-Pad2)") (class "Default")
      (node (ref "R40") (pin "2") (pinfunction "2_2") (pintype "passive"))
      (node (ref "R41") (pin "1") (pinfunction "1_1") (pintype "passive"))
    )
    (net (code "77") (name "Net-(R42-Pad2)") (class "Default")
      (node (ref "R42") (pin "2") (pinfunction "2_2") (pintype "passive"))
      (node (ref "R43") (pin "1") (pinfunction "1_1") (pintype "passive"))
    )
    (net (code "78") (name "Net-(R43-Pad2)") (class "Default")
      (node (ref "R43") (pin "2") (pinfunction "2_2") (pintype "passive"))
      (node (ref "R44") (pin "1") (pinfunction "1_1") (pintype "passive"))
    )
    (net (code "79") (name "Net-(R45-Pad2)") (class "Default")
      (node (ref "R45") (pin "2") (pinfunction "2_2") (pintype "passive"))
      (node (ref "R46") (pin "1") (pinfunction "1_1") (pintype "passive"))
    )
    (net (code "80") (name "Net-(R47-Pad1)") (class "Default")
      (node (ref "R47") (pin "1") (pinfunction "1_1") (pintype "passive"))
      (node (ref "R6") (pin "2") (pinfunction "2_2") (pintype "passive"))
    )
    (net (code "81") (name "Net-(R47-Pad2)") (class "Default")
      (node (ref "R47") (pin "2") (pinfunction "2_2") (pintype "passive"))
      (node (ref "R48") (pin "1") (pinfunction "1_1") (pintype "passive"))
    )
    (net (code "82") (name "Net-(R49-Pad2)") (class "Default")
      (node (ref "R49") (pin "2") (pinfunction "2_2") (pintype "passive"))
      (node (ref "R50") (pin "1") (pinfunction "1_1") (pintype "passive"))
    )
    (net (code "83") (name "Net-(R51-Pad2)") (class "Default")
      (node (ref "R51") (pin "2") (pinfunction "2_2") (pintype "passive"))
      (node (ref "R55") (pin "2") (pinfunction "2_2") (pintype "passive"))
    )
    (net (code "84") (name "Net-(R52-Pad2)") (class "Default")
      (node (ref "R52") (pin "2") (pinfunction "2_2") (pintype "passive"))
      (node (ref "R53") (pin "1") (pinfunction "1_1") (pintype "passive"))
    )
    (net (code "85") (name "Net-(R53-Pad2)") (class "Default")
      (node (ref "R53") (pin "2") (pinfunction "2_2") (pintype "passive"))
      (node (ref "R56") (pin "2") (pinfunction "2_2") (pintype "passive"))
    )
  )
)
